# Pressure.net
KiCad netlist of a schematic drawn in Altium Designer
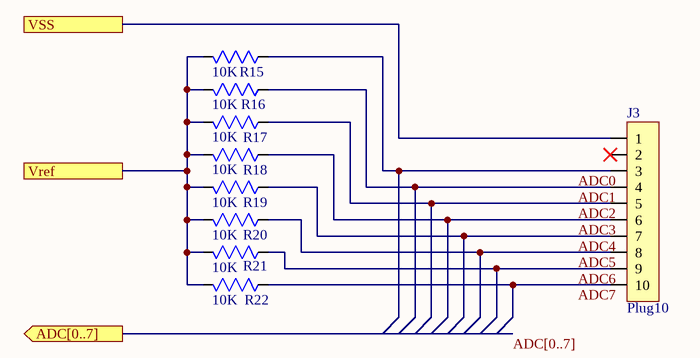
[diagram p0: Pressure.SchDoc]

(export (version "E")
  (design (tool "Eeschema 10.0.6"))
  (components
    (comp (ref "J3") (value "Plug10") (footprint "FPC0.5-10PS") (libsource (lib "ZGR") (part "Plug10")))
    (comp (ref "R15")
      (value "10K")
      (footprint "RES_0402")
      (fields (field (name "Comment") "Res"))
      (libsource (lib "ZGR") (part "Res"))
    )
    (comp (ref "R16")
      (value "10K")
      (footprint "RES_0402")
      (fields (field (name "Comment") "Res"))
      (libsource (lib "ZGR") (part "Res"))
    )
    (comp (ref "R17")
      (value "10K")
      (footprint "RES_0402")
      (fields (field (name "Comment") "Res"))
      (libsource (lib "ZGR") (part "Res"))
    )
    (comp (ref "R18")
      (value "10K")
      (footprint "RES_0402")
      (fields (field (name "Comment") "Res"))
      (libsource (lib "ZGR") (part "Res"))
    )
    (comp (ref "R19")
      (value "10K")
      (footprint "RES_0402")
      (fields (field (name "Comment") "Res"))
      (libsource (lib "ZGR") (part "Res"))
    )
    (comp (ref "R20")
      (value "10K")
      (footprint "RES_0402")
      (fields (field (name "Comment") "Res"))
      (libsource (lib "ZGR") (part "Res"))
    )
    (comp (ref "R21")
      (value "10K")
      (footprint "RES_0402")
      (fields (field (name "Comment") "Res"))
      (libsource (lib "ZGR") (part "Res"))
    )
    (comp (ref "R22")
      (value "10K")
      (footprint "RES_0402")
      (fields (field (name "Comment") "Res"))
      (libsource (lib "ZGR") (part "Res"))
    )
  )
  (nets
    (net (code "1") (name "/ADC0") (class "Default")
      (node (ref "J3") (pin "3") (pinfunction "3_3") (pintype "passive"))
      (node (ref "R15") (pin "2") (pinfunction "2_2") (pintype "passive"))
    )
    (net (code "2") (name "/ADC1") (class "Default")
      (node (ref "J3") (pin "4") (pinfunction "4_4") (pintype "passive"))
      (node (ref "R16") (pin "2") (pinfunction "2_2") (pintype "passive"))
    )
    (net (code "3") (name "/ADC2") (class "Default")
      (node (ref "J3") (pin "5") (pinfunction "5_5") (pintype "passive"))
      (node (ref "R17") (pin "2") (pinfunction "2_2") (pintype "passive"))
    )
    (net (code "4") (name "/ADC3") (class "Default")
      (node (ref "J3") (pin "6") (pinfunction "6_6") (pintype "passive"))
      (node (ref "R18") (pin "2") (pinfunction "2_2") (pintype "passive"))
    )
    (net (code "5") (name "/ADC4") (class "Default")
      (node (ref "J3") (pin "7") (pinfunction "7_7") (pintype "passive"))
      (node (ref "R19") (pin "2") (pinfunction "2_2") (pintype "passive"))
    )
    (net (code "6") (name "/ADC5") (class "Default")
      (node (ref "J3") (pin "8") (pinfunction "8_8") (pintype "passive"))
      (node (ref "R20") (pin "2") (pinfunction "2_2") (pintype "passive"))
    )
    (net (code "7") (name "/ADC6") (class "Default")
      (node (ref "J3") (pin "9") (pinfunction "9_9") (pintype "passive"))
      (node (ref "R21") (pin "2") (pinfunction "2_2") (pintype "passive"))
    )
    (net (code "8") (name "/ADC7") (class "Default")
      (node (ref "J3") (pin "10") (pinfunction "10_10") (pintype "passive"))
      (node (ref "R22") (pin "2") (pinfunction "2_2") (pintype "passive"))
    )
    (net (code "10") (name "/VSS") (class "Default")
      (node (ref "J3") (pin "1") (pinfunction "1_1") (pintype "passive"))
    )
    (net (code "11") (name "/Vref") (class "Default")
      (node (ref "R15") (pin "1") (pinfunction "1_1") (pintype "passive"))
      (node (ref "R16") (pin "1") (pinfunction "1_1") (pintype "passive"))
      (node (ref "R17") (pin "1") (pinfunction "1_1") (pintype "passive"))
      (node (ref "R18") (pin "1") (pinfunction "1_1") (pintype "passive"))
      (node (ref "R19") (pin "1") (pinfunction "1_1") (pintype "passive"))
      (node (ref "R20") (pin "1") (pinfunction "1_1") (pintype "passive"))
      (node (ref "R21") (pin "1") (pinfunction "1_1") (pintype "passive"))
      (node (ref "R22") (pin "1") (pinfunction "1_1") (pintype "passive"))
    )
    (net (code "12") (name "unconnected-(J3-Pad2)") (class "Default")
      (node (ref "J3") (pin "2") (pinfunction "2_2") (pintype "passive+no_connect"))
    )
  )
)
